# Quad-Stage-Prototype_V1_0.net
KiCad netlist of a schematic drawn in Altium Designer
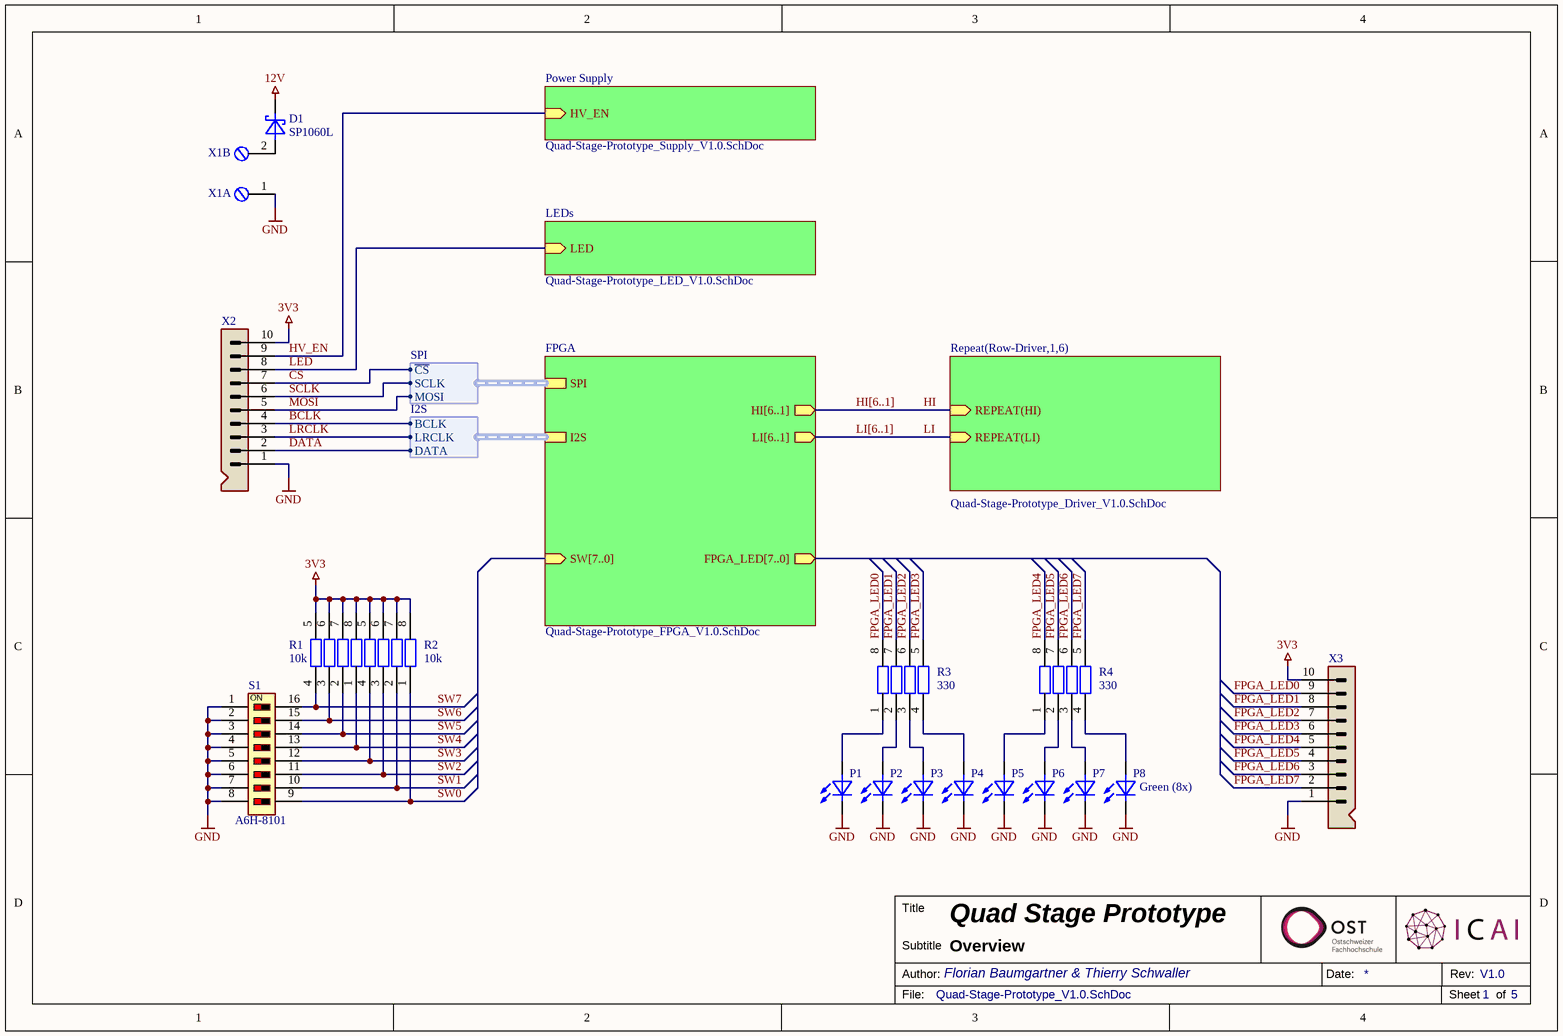
[diagram p0: Quad-Stage-Prototype_V1.0.SchDoc]

(export (version "E")
  (design (tool "Eeschema 10.0.6"))
  (components
    (comp (ref "D1")
      (value "SP1060L")
      (footprint "SMD Diode TO-277")
      (description "S-DIODE")
      (libsource (lib "TFS Integrated Library") (part "R-DIODE{colon}SCHKY"))
    )
    (comp (ref "P1")
      (value "Green")
      (footprint "SMD LED 0603")
      (description "General Purpose LED")
      (libsource (lib "Fleet-Monitor") (part "LED Green 0603"))
    )
    (comp (ref "P2")
      (value "Green")
      (footprint "SMD LED 0603")
      (description "General Purpose LED")
      (libsource (lib "Fleet-Monitor") (part "LED Green 0603"))
    )
    (comp (ref "P3")
      (value "Green")
      (footprint "SMD LED 0603")
      (description "General Purpose LED")
      (libsource (lib "Fleet-Monitor") (part "LED Green 0603"))
    )
    (comp (ref "P4")
      (value "Green")
      (footprint "SMD LED 0603")
      (description "General Purpose LED")
      (libsource (lib "Fleet-Monitor") (part "LED Green 0603"))
    )
    (comp (ref "P5")
      (value "Green")
      (footprint "SMD LED 0603")
      (description "General Purpose LED")
      (libsource (lib "Fleet-Monitor") (part "LED Green 0603"))
    )
    (comp (ref "P6")
      (value "Green")
      (footprint "SMD LED 0603")
      (description "General Purpose LED")
      (libsource (lib "Fleet-Monitor") (part "LED Green 0603"))
    )
    (comp (ref "P7")
      (value "Green")
      (footprint "SMD LED 0603")
      (description "General Purpose LED")
      (libsource (lib "Fleet-Monitor") (part "LED Green 0603"))
    )
    (comp (ref "P8")
      (value "Green")
      (footprint "SMD LED 0603")
      (description "General Purpose LED")
      (libsource (lib "Fleet-Monitor") (part "LED Green 0603"))
    )
    (comp (ref "R1")
      (value "10k")
      (footprint "SMD Widerstand Array 4-Fach 0603")
      (description "Isolated Resistor Array")
      (libsource (lib "Fleet-Monitor") (part "R-Array Single Quad E24 - 10k"))
    )
    (comp (ref "R2")
      (value "10k")
      (footprint "SMD Widerstand Array 4-Fach 0603")
      (description "Isolated Resistor Array")
      (libsource (lib "Fleet-Monitor") (part "R-Array Single Quad E24 - 10k"))
    )
    (comp (ref "R3")
      (value "330")
      (footprint "SMD Widerstand Array 4-Fach 0603")
      (description "Isolated Resistor Array")
      (libsource (lib "Fleet-Monitor") (part "R-Array Single Quad E24 - 330"))
    )
    (comp (ref "R4")
      (value "330")
      (footprint "SMD Widerstand Array 4-Fach 0603")
      (description "Isolated Resistor Array")
      (libsource (lib "Fleet-Monitor") (part "R-Array Single Quad E24 - 330"))
    )
    (comp (ref "S1")
      (value "A6H-8101")
      (footprint "SMD DIP-Switch 8-Pos")
      (description "DIP-Switch 8 Positions")
      (libsource (lib "Quad-Stage-Prototype") (part "S-A6H-8101"))
    )
    (comp (ref "X1")
      (value "X-Klemme (2-Pol)")
      (footprint "THT Schraubklemme 2-Pol (WJ500V-5.08-2P)")
      (libsource (lib "Quad-Current-Probe") (part "X-Klemme (2-Pol)"))
    )
    (comp (ref "X2")
      (value "Stiftleiste (10-Fach)")
      (footprint "THT Pin-Header 10x1 (90°)")
      (libsource (lib "") (part "X-Stiftleiste (10-Fach)_1"))
    )
    (comp (ref "X3")
      (value "Stiftleiste (10-Fach)")
      (footprint "THT Pin-Header 10x1 (90°)")
      (libsource (lib "Quad-Stage-Prototype") (part "X-Stiftleiste (10-Fach)"))
    )
  )
  (nets
    (net (code "15") (name "/BCLK") (class "Default")
      (node (ref "X2") (pin "4") (pinfunction "4_4") (pintype "passive"))
    )
    (net (code "16") (name "/DATA") (class "Default")
      (node (ref "X2") (pin "2") (pinfunction "2_2") (pintype "passive"))
    )
    (net (code "17") (name "/FPGA_LED0") (class "Default")
      (node (ref "R3") (pin "8") (pinfunction "8_8") (pintype "passive"))
      (node (ref "X3") (pin "9") (pinfunction "9_9") (pintype "passive"))
    )
    (net (code "18") (name "/FPGA_LED1") (class "Default")
      (node (ref "R3") (pin "7") (pinfunction "7_7") (pintype "passive"))
      (node (ref "X3") (pin "8") (pinfunction "8_8") (pintype "passive"))
    )
    (net (code "19") (name "/FPGA_LED2") (class "Default")
      (node (ref "R3") (pin "6") (pinfunction "6_6") (pintype "passive"))
      (node (ref "X3") (pin "7") (pinfunction "7_7") (pintype "passive"))
    )
    (net (code "20") (name "/FPGA_LED3") (class "Default")
      (node (ref "R3") (pin "5") (pinfunction "5_5") (pintype "passive"))
      (node (ref "X3") (pin "6") (pinfunction "6_6") (pintype "passive"))
    )
    (net (code "21") (name "/FPGA_LED4") (class "Default")
      (node (ref "R4") (pin "8") (pinfunction "8_8") (pintype "passive"))
      (node (ref "X3") (pin "5") (pinfunction "5_5") (pintype "passive"))
    )
    (net (code "22") (name "/FPGA_LED5") (class "Default")
      (node (ref "R4") (pin "7") (pinfunction "7_7") (pintype "passive"))
      (node (ref "X3") (pin "4") (pinfunction "4_4") (pintype "passive"))
    )
    (net (code "23") (name "/FPGA_LED6") (class "Default")
      (node (ref "R4") (pin "6") (pinfunction "6_6") (pintype "passive"))
      (node (ref "X3") (pin "3") (pinfunction "3_3") (pintype "passive"))
    )
    (net (code "24") (name "/FPGA_LED7") (class "Default")
      (node (ref "R4") (pin "5") (pinfunction "5_5") (pintype "passive"))
      (node (ref "X3") (pin "2") (pinfunction "2_2") (pintype "passive"))
    )
    (net (code "28") (name "/HV_EN") (class "Default")
      (node (ref "X2") (pin "9") (pinfunction "9_9") (pintype "passive"))
    )
    (net (code "29") (name "/LED") (class "Default")
      (node (ref "X2") (pin "8") (pinfunction "8_8") (pintype "passive"))
    )
    (net (code "32") (name "/LRCLK") (class "Default")
      (node (ref "X2") (pin "3") (pinfunction "3_3") (pintype "passive"))
    )
    (net (code "33") (name "/MOSI") (class "Default")
      (node (ref "X2") (pin "5") (pinfunction "5_5") (pintype "passive"))
    )
    (net (code "34") (name "/SCLK") (class "Default")
      (node (ref "X2") (pin "6") (pinfunction "6_6") (pintype "passive"))
    )
    (net (code "35") (name "/SW0") (class "Default")
      (node (ref "R2") (pin "1") (pinfunction "1_1") (pintype "passive"))
      (node (ref "S1") (pin "9") (pinfunction "9_9") (pintype "passive"))
    )
    (net (code "36") (name "/SW1") (class "Default")
      (node (ref "R2") (pin "2") (pinfunction "2_2") (pintype "passive"))
      (node (ref "S1") (pin "10") (pinfunction "10_10") (pintype "passive"))
    )
    (net (code "37") (name "/SW2") (class "Default")
      (node (ref "R2") (pin "3") (pinfunction "3_3") (pintype "passive"))
      (node (ref "S1") (pin "11") (pinfunction "11_11") (pintype "passive"))
    )
    (net (code "38") (name "/SW3") (class "Default")
      (node (ref "R2") (pin "4") (pinfunction "4_4") (pintype "passive"))
      (node (ref "S1") (pin "12") (pinfunction "12_12") (pintype "passive"))
    )
    (net (code "39") (name "/SW4") (class "Default")
      (node (ref "R1") (pin "1") (pinfunction "1_1") (pintype "passive"))
      (node (ref "S1") (pin "13") (pinfunction "13_13") (pintype "passive"))
    )
    (net (code "40") (name "/SW5") (class "Default")
      (node (ref "R1") (pin "2") (pinfunction "2_2") (pintype "passive"))
      (node (ref "S1") (pin "14") (pinfunction "14_14") (pintype "passive"))
    )
    (net (code "41") (name "/SW6") (class "Default")
      (node (ref "R1") (pin "3") (pinfunction "3_3") (pintype "passive"))
      (node (ref "S1") (pin "15") (pinfunction "15_15") (pintype "passive"))
    )
    (net (code "42") (name "/SW7") (class "Default")
      (node (ref "R1") (pin "4") (pinfunction "4_4") (pintype "passive"))
      (node (ref "S1") (pin "16") (pinfunction "16_16") (pintype "passive"))
    )
    (net (code "46") (name "/~{CS}") (class "Default")
      (node (ref "X2") (pin "7") (pinfunction "7_7") (pintype "passive"))
    )
    (net (code "47") (name "3V3") (class "Default")
      (node (ref "R1") (pin "5") (pinfunction "5_5") (pintype "passive"))
      (node (ref "R1") (pin "6") (pinfunction "6_6") (pintype "passive"))
      (node (ref "R1") (pin "7") (pinfunction "7_7") (pintype "passive"))
      (node (ref "R1") (pin "8") (pinfunction "8_8") (pintype "passive"))
      (node (ref "R2") (pin "5") (pinfunction "5_5") (pintype "passive"))
      (node (ref "R2") (pin "6") (pinfunction "6_6") (pintype "passive"))
      (node (ref "R2") (pin "7") (pinfunction "7_7") (pintype "passive"))
      (node (ref "R2") (pin "8") (pinfunction "8_8") (pintype "passive"))
      (node (ref "X2") (pin "10") (pinfunction "10_10") (pintype "passive"))
      (node (ref "X3") (pin "10") (pinfunction "10_10") (pintype "passive"))
    )
    (net (code "48") (name "12V") (class "Default")
      (node (ref "D1") (pin "K") (pinfunction "K_K") (pintype "passive"))
    )
    (net (code "49") (name "GND") (class "Default")
      (node (ref "P1") (pin "K") (pinfunction "K_K") (pintype "passive"))
      (node (ref "P2") (pin "K") (pinfunction "K_K") (pintype "passive"))
      (node (ref "P3") (pin "K") (pinfunction "K_K") (pintype "passive"))
      (node (ref "P4") (pin "K") (pinfunction "K_K") (pintype "passive"))
      (node (ref "P5") (pin "K") (pinfunction "K_K") (pintype "passive"))
      (node (ref "P6") (pin "K") (pinfunction "K_K") (pintype "passive"))
      (node (ref "P7") (pin "K") (pinfunction "K_K") (pintype "passive"))
      (node (ref "P8") (pin "K") (pinfunction "K_K") (pintype "passive"))
      (node (ref "S1") (pin "1") (pinfunction "1_1") (pintype "passive"))
      (node (ref "S1") (pin "2") (pinfunction "2_2") (pintype "passive"))
      (node (ref "S1") (pin "3") (pinfunction "3_3") (pintype "passive"))
      (node (ref "S1") (pin "4") (pinfunction "4_4") (pintype "passive"))
      (node (ref "S1") (pin "5") (pinfunction "5_5") (pintype "passive"))
      (node (ref "S1") (pin "6") (pinfunction "6_6") (pintype "passive"))
      (node (ref "S1") (pin "7") (pinfunction "7_7") (pintype "passive"))
      (node (ref "S1") (pin "8") (pinfunction "8_8") (pintype "passive"))
      (node (ref "X1") (pin "1") (pinfunction "1_1") (pintype "passive"))
      (node (ref "X2") (pin "1") (pinfunction "1_1") (pintype "passive"))
      (node (ref "X3") (pin "1") (pinfunction "1_1") (pintype "passive"))
    )
    (net (code "50") (name "Net-(D1-PadA)") (class "Default")
      (node (ref "D1") (pin "A") (pinfunction "A_A") (pintype "passive"))
      (node (ref "X1") (pin "2") (pinfunction "2_2") (pintype "passive"))
    )
    (net (code "51") (name "Net-(P1-PadA)") (class "Default")
      (node (ref "P1") (pin "A") (pinfunction "A_A") (pintype "passive"))
      (node (ref "R3") (pin "1") (pinfunction "1_1") (pintype "passive"))
    )
    (net (code "52") (name "Net-(P2-PadA)") (class "Default")
      (node (ref "P2") (pin "A") (pinfunction "A_A") (pintype "passive"))
      (node (ref "R3") (pin "2") (pinfunction "2_2") (pintype "passive"))
    )
    (net (code "53") (name "Net-(P3-PadA)") (class "Default")
      (node (ref "P3") (pin "A") (pinfunction "A_A") (pintype "passive"))
      (node (ref "R3") (pin "3") (pinfunction "3_3") (pintype "passive"))
    )
    (net (code "54") (name "Net-(P4-PadA)") (class "Default")
      (node (ref "P4") (pin "A") (pinfunction "A_A") (pintype "passive"))
      (node (ref "R3") (pin "4") (pinfunction "4_4") (pintype "passive"))
    )
    (net (code "55") (name "Net-(P5-PadA)") (class "Default")
      (node (ref "P5") (pin "A") (pinfunction "A_A") (pintype "passive"))
      (node (ref "R4") (pin "1") (pinfunction "1_1") (pintype "passive"))
    )
    (net (code "56") (name "Net-(P6-PadA)") (class "Default")
      (node (ref "P6") (pin "A") (pinfunction "A_A") (pintype "passive"))
      (node (ref "R4") (pin "2") (pinfunction "2_2") (pintype "passive"))
    )
    (net (code "57") (name "Net-(P7-PadA)") (class "Default")
      (node (ref "P7") (pin "A") (pinfunction "A_A") (pintype "passive"))
      (node (ref "R4") (pin "3") (pinfunction "3_3") (pintype "passive"))
    )
    (net (code "58") (name "Net-(P8-PadA)") (class "Default")
      (node (ref "P8") (pin "A") (pinfunction "A_A") (pintype "passive"))
      (node (ref "R4") (pin "4") (pinfunction "4_4") (pintype "passive"))
    )
  )
)
